# Circuit_schematic.net
KiCad netlist of a schematic drawn in EAGLE
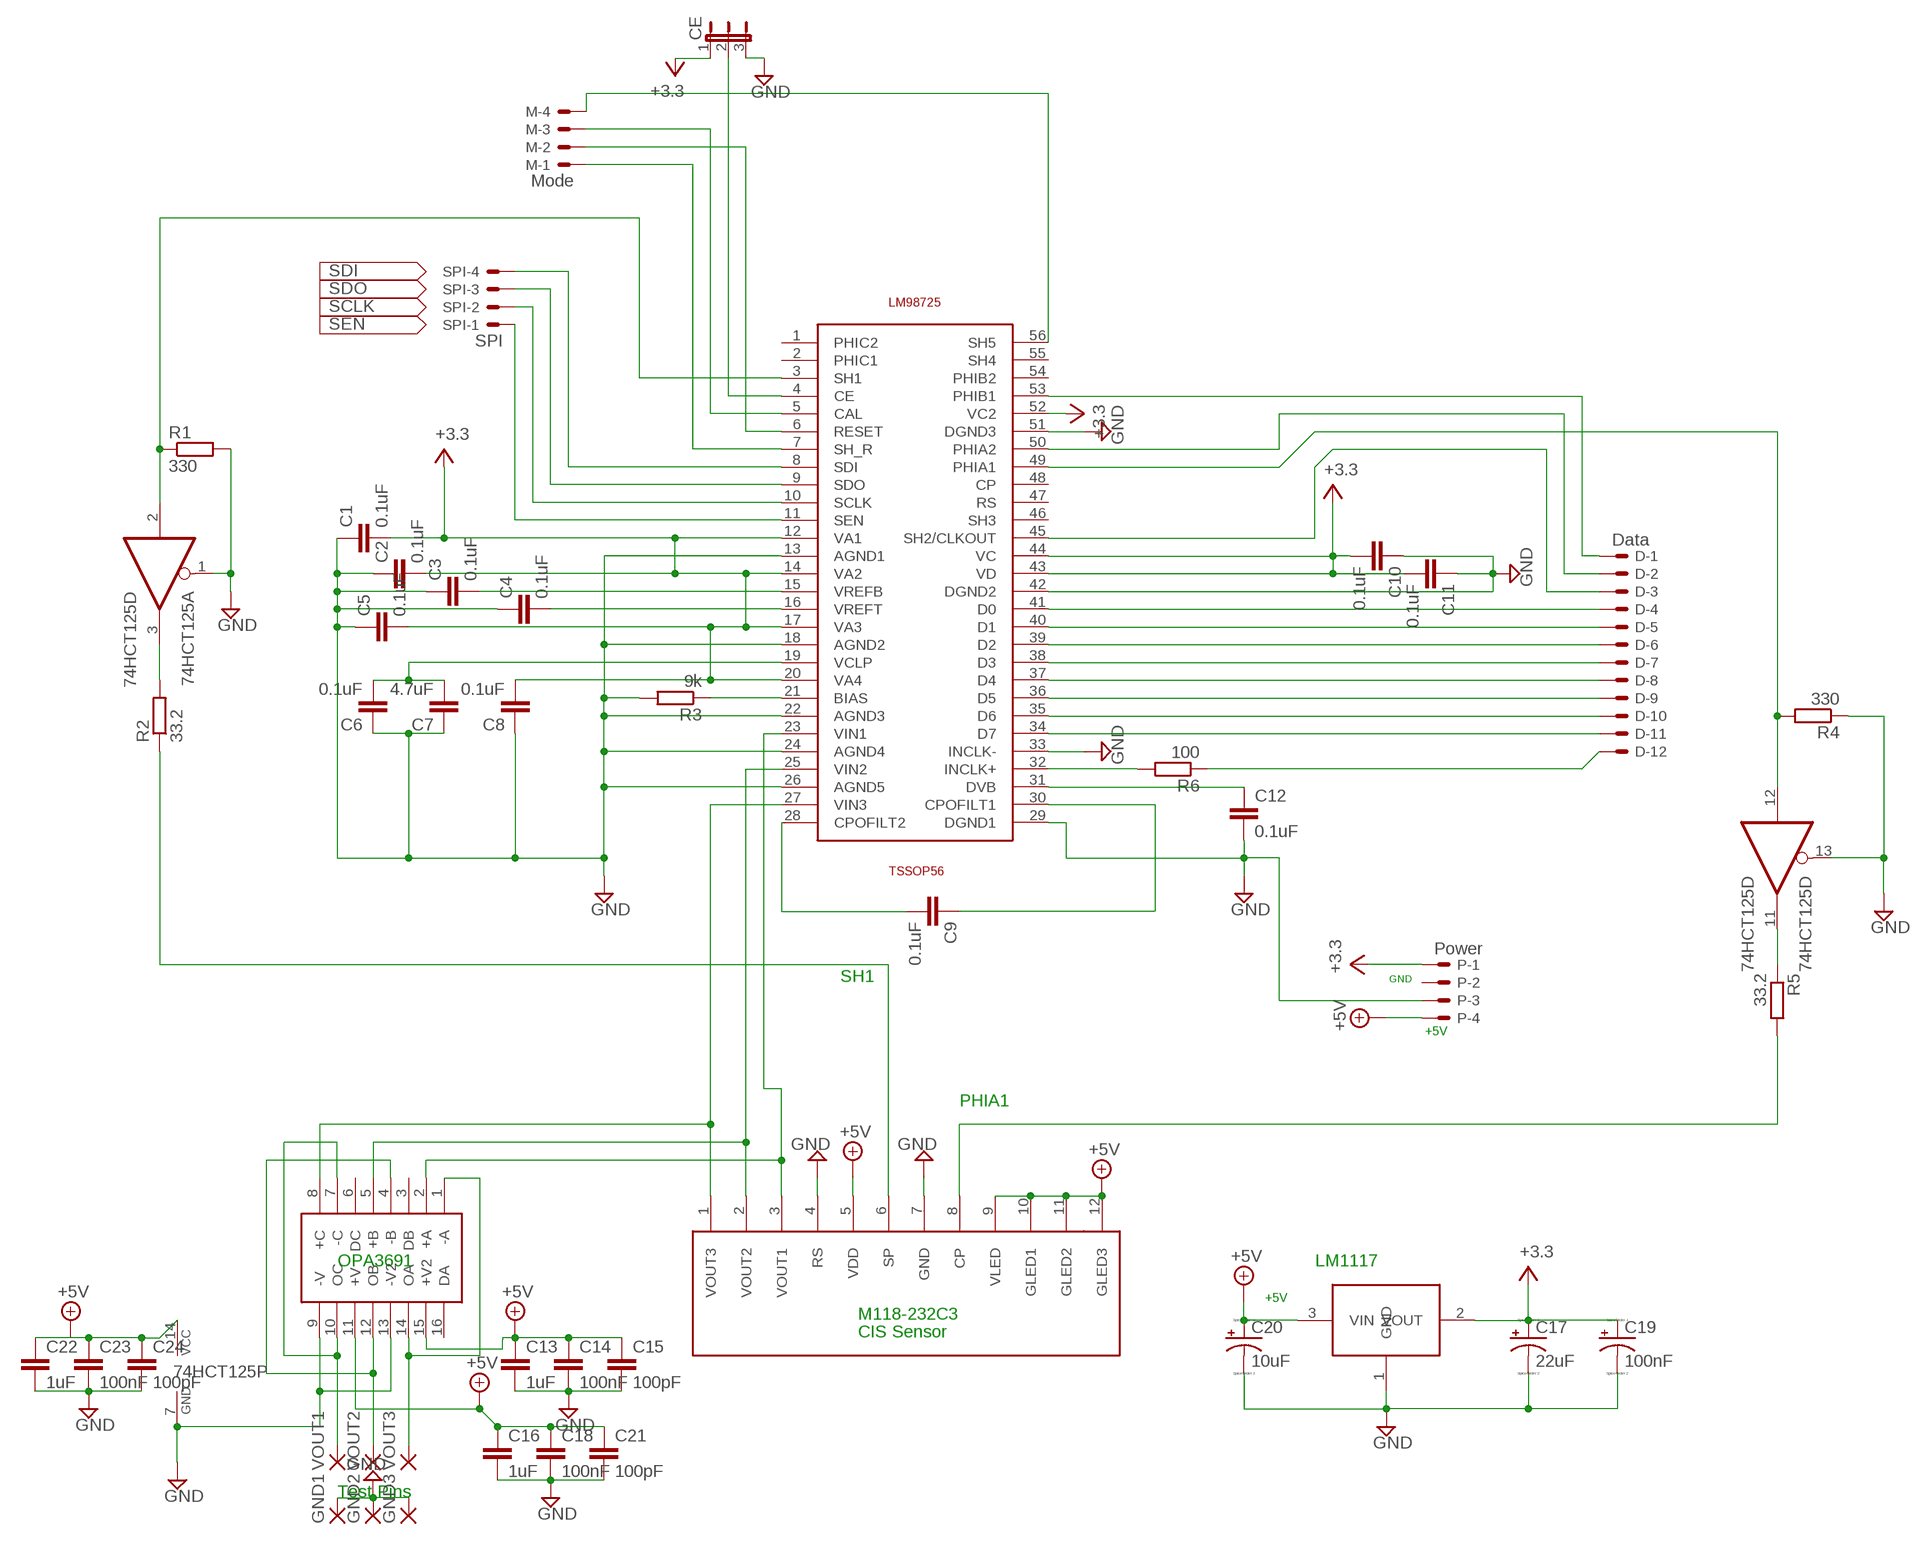
[diagram p0: schematic, sheet 1]

(export (version "E")
  (design (tool "Eeschema 10.0.6"))
  (components
    (comp (ref "74HCT125")
      (value "74HCT125D")
      (footprint "eagle-import:SO14")
      (libsource (lib "eagle-import") (part "74125DHCT"))
    )
    (comp (ref "C1")
      (value "0.1uF")
      (footprint "eagle-import:C0603")
      (libsource (lib "eagle-import") (part "C-EUC0603"))
    )
    (comp (ref "C2")
      (value "0.1uF")
      (footprint "eagle-import:C0603")
      (libsource (lib "eagle-import") (part "C-EUC0603"))
    )
    (comp (ref "C3")
      (value "0.1uF")
      (footprint "eagle-import:C0603")
      (libsource (lib "eagle-import") (part "C-EUC0603"))
    )
    (comp (ref "C4")
      (value "0.1uF")
      (footprint "eagle-import:C0603")
      (libsource (lib "eagle-import") (part "C-EUC0603"))
    )
    (comp (ref "C5")
      (value "0.1uF")
      (footprint "eagle-import:C0603")
      (libsource (lib "eagle-import") (part "C-EUC0603"))
    )
    (comp (ref "C6")
      (value "0.1uF")
      (footprint "eagle-import:C0603")
      (libsource (lib "eagle-import") (part "C-EUC0603"))
    )
    (comp (ref "C7")
      (value "4.7uF")
      (footprint "eagle-import:C0603")
      (libsource (lib "eagle-import") (part "C-EUC0603"))
    )
    (comp (ref "C8")
      (value "0.1uF")
      (footprint "eagle-import:C0603")
      (libsource (lib "eagle-import") (part "C-EUC0603"))
    )
    (comp (ref "C9")
      (value "0.1uF")
      (footprint "eagle-import:C0603")
      (libsource (lib "eagle-import") (part "C-EUC0603"))
    )
    (comp (ref "C10")
      (value "0.1uF")
      (footprint "eagle-import:C0603")
      (libsource (lib "eagle-import") (part "C-EUC0603"))
    )
    (comp (ref "C11")
      (value "0.1uF")
      (footprint "eagle-import:C0603")
      (libsource (lib "eagle-import") (part "C-EUC0603"))
    )
    (comp (ref "C12")
      (value "0.1uF")
      (footprint "eagle-import:C0603")
      (libsource (lib "eagle-import") (part "C-EUC0603"))
    )
    (comp (ref "C13")
      (value "1uF")
      (footprint "eagle-import:C0603")
      (libsource (lib "eagle-import") (part "C-EUC0603"))
    )
    (comp (ref "C14")
      (value "100nF")
      (footprint "eagle-import:C0603")
      (libsource (lib "eagle-import") (part "C-EUC0603"))
    )
    (comp (ref "C15")
      (value "100pF")
      (footprint "eagle-import:C0603")
      (libsource (lib "eagle-import") (part "C-EUC0603"))
    )
    (comp (ref "C16")
      (value "1uF")
      (footprint "eagle-import:C0603")
      (libsource (lib "eagle-import") (part "C-EUC0603"))
    )
    (comp (ref "C17")
      (value "22uF")
      (footprint "eagle-import:D_7343-31W")
      (libsource (lib "eagle-import") (part "CPOL-USD/7343-31W"))
    )
    (comp (ref "C18")
      (value "100nF")
      (footprint "eagle-import:C0603")
      (libsource (lib "eagle-import") (part "C-EUC0603"))
    )
    (comp (ref "C19")
      (value "100nF")
      (footprint "eagle-import:A_3216-18W")
      (libsource (lib "eagle-import") (part "CPOL-USA/3216-18W"))
    )
    (comp (ref "C20")
      (value "10uF")
      (footprint "eagle-import:C_6032-28R")
      (libsource (lib "eagle-import") (part "CPOL-USC/6032-28R"))
    )
    (comp (ref "C21")
      (value "100pF")
      (footprint "eagle-import:C0603")
      (libsource (lib "eagle-import") (part "C-EUC0603"))
    )
    (comp (ref "C22")
      (value "1uF")
      (footprint "eagle-import:C0603")
      (libsource (lib "eagle-import") (part "C-EUC0603"))
    )
    (comp (ref "C23")
      (value "100nF")
      (footprint "eagle-import:C0603")
      (libsource (lib "eagle-import") (part "C-EUC0603"))
    )
    (comp (ref "C24")
      (value "100pF")
      (footprint "eagle-import:C0603")
      (libsource (lib "eagle-import") (part "C-EUC0603"))
    )
    (comp (ref "CE")
      (value "JP2E")
      (footprint "eagle-import:JP2")
      (libsource (lib "eagle-import") (part "JP2E"))
    )
    (comp (ref "D")
      (value "Data")
      (footprint "eagle-import:53048-12")
      (fields (field (name "MF") "WALDOM/MOLEX") (field (name "MPN") "53048-1210"))
      (libsource (lib "eagle-import") (part "53?-12048"))
    )
    (comp (ref "GND1")
      (value "3,17/1,3")
      (footprint "eagle-import:3,17_1,3")
      (libsource (lib "eagle-import") (part "3,17/1,3"))
    )
    (comp (ref "GND2")
      (value "3,17/1,3")
      (footprint "eagle-import:3,17_1,3")
      (libsource (lib "eagle-import") (part "3,17/1,3"))
    )
    (comp (ref "GND3")
      (value "3,17/1,3")
      (footprint "eagle-import:3,17_1,3")
      (libsource (lib "eagle-import") (part "3,17/1,3"))
    )
    (comp (ref "LM98725")
      (value "LM98725")
      (footprint "eagle-import:TSSOP56")
      (libsource (lib "eagle-import") (part "LM98725"))
    )
    (comp (ref "M")
      (value "Mode")
      (footprint "eagle-import:53048-04")
      (fields (field (name "MF") "MOLEX") (field (name "MPN") "53048-0410"))
      (libsource (lib "eagle-import") (part "53?-04048"))
    )
    (comp (ref "OPA3691")
      (value "OPA3691")
      (footprint "eagle-import:SO16")
      (libsource (lib "eagle-import") (part "OPA3691"))
    )
    (comp (ref "P")
      (value "Power")
      (footprint "eagle-import:53048-04")
      (fields (field (name "MF") "MOLEX") (field (name "MPN") "53048-0410"))
      (libsource (lib "eagle-import") (part "53?-04048"))
    )
    (comp (ref "R1")
      (value "330")
      (footprint "eagle-import:R0603")
      (libsource (lib "eagle-import") (part "R-EU_R0603"))
    )
    (comp (ref "R2")
      (value "33.2")
      (footprint "eagle-import:R0603")
      (libsource (lib "eagle-import") (part "R-EU_R0603"))
    )
    (comp (ref "R3")
      (value "9k")
      (footprint "eagle-import:R0603")
      (libsource (lib "eagle-import") (part "R-EU_R0603"))
    )
    (comp (ref "R4")
      (value "330")
      (footprint "eagle-import:R0603")
      (libsource (lib "eagle-import") (part "R-EU_R0603"))
    )
    (comp (ref "R5")
      (value "33.2")
      (footprint "eagle-import:R0603")
      (libsource (lib "eagle-import") (part "R-EU_R0603"))
    )
    (comp (ref "R6")
      (value "100")
      (footprint "eagle-import:R0603")
      (libsource (lib "eagle-import") (part "R-EU_R0603"))
    )
    (comp (ref "SENSOR")
      (value "CIS-M118118")
      (footprint "eagle-import:12PINPAD")
      (libsource (lib "eagle-import") (part "CIS-M118118"))
    )
    (comp (ref "SPI")
      (value "SPI")
      (footprint "eagle-import:53048-04")
      (fields (field (name "MF") "MOLEX") (field (name "MPN") "53048-0410"))
      (libsource (lib "eagle-import") (part "53?-04048"))
    )
    (comp (ref "U$2")
      (value "LM117")
      (footprint "eagle-import:LM")
      (libsource (lib "eagle-import") (part "LM117"))
    )
    (comp (ref "VOUT1")
      (value "3,17/1,3")
      (footprint "eagle-import:3,17_1,3")
      (libsource (lib "eagle-import") (part "3,17/1,3"))
    )
    (comp (ref "VOUT2")
      (value "3,17/1,3")
      (footprint "eagle-import:3,17_1,3")
      (libsource (lib "eagle-import") (part "3,17/1,3"))
    )
    (comp (ref "VOUT3")
      (value "3,17/1,3")
      (footprint "eagle-import:3,17_1,3")
      (libsource (lib "eagle-import") (part "3,17/1,3"))
    )
  )
  (nets
    (net (code "1") (name "+3.3") (class "Default")
      (node (ref "C1") (pin "2") (pinfunction "2_2") (pintype "passive"))
      (node (ref "C10") (pin "2") (pinfunction "2_2") (pintype "passive"))
      (node (ref "C11") (pin "2") (pinfunction "2_2") (pintype "passive"))
      (node (ref "C17") (pin "+") (pinfunction "+_+") (pintype "passive"))
      (node (ref "C19") (pin "+") (pinfunction "+_+") (pintype "passive"))
      (node (ref "C2") (pin "2") (pinfunction "2_2") (pintype "passive"))
      (node (ref "C5") (pin "2") (pinfunction "2_2") (pintype "passive"))
      (node (ref "C8") (pin "2") (pinfunction "2_2") (pintype "passive"))
      (node (ref "CE") (pin "1") (pinfunction "1_1") (pintype "passive"))
      (node (ref "LM98725") (pin "12") (pinfunction "VA1_12") (pintype "bidirectional"))
      (node (ref "LM98725") (pin "14") (pinfunction "VA2_14") (pintype "bidirectional"))
      (node (ref "LM98725") (pin "17") (pinfunction "VA3_17") (pintype "bidirectional"))
      (node (ref "LM98725") (pin "20") (pinfunction "VA4_20") (pintype "bidirectional"))
      (node (ref "LM98725") (pin "43") (pinfunction "VD_43") (pintype "bidirectional"))
      (node (ref "LM98725") (pin "44") (pinfunction "VC_44") (pintype "bidirectional"))
      (node (ref "LM98725") (pin "52") (pinfunction "VC2_52") (pintype "bidirectional"))
      (node (ref "P") (pin "1") (pinfunction "S_1") (pintype "passive"))
      (node (ref "U$2") (pin "2") (pinfunction "VOUT_2") (pintype "bidirectional"))
    )
    (net (code "2") (name "+5V") (class "Default")
      (node (ref "74HCT125") (pin "14") (pinfunction "VCC_14") (pintype "power_in"))
      (node (ref "C13") (pin "1") (pinfunction "1_1") (pintype "passive"))
      (node (ref "C14") (pin "1") (pinfunction "1_1") (pintype "passive"))
      (node (ref "C15") (pin "1") (pinfunction "1_1") (pintype "passive"))
      (node (ref "C16") (pin "1") (pinfunction "1_1") (pintype "passive"))
      (node (ref "C18") (pin "1") (pinfunction "1_1") (pintype "passive"))
      (node (ref "C20") (pin "+") (pinfunction "+_+") (pintype "passive"))
      (node (ref "C21") (pin "1") (pinfunction "1_1") (pintype "passive"))
      (node (ref "C22") (pin "1") (pinfunction "1_1") (pintype "passive"))
      (node (ref "C23") (pin "1") (pinfunction "1_1") (pintype "passive"))
      (node (ref "C24") (pin "1") (pinfunction "1_1") (pintype "passive"))
      (node (ref "OPA3691") (pin "11") (pinfunction "+V_11") (pintype "bidirectional"))
      (node (ref "OPA3691") (pin "15") (pinfunction "+V2_15") (pintype "bidirectional"))
      (node (ref "P") (pin "4") (pinfunction "S_4") (pintype "passive"))
      (node (ref "SENSOR") (pin "10") (pinfunction "GLED1_10") (pintype "bidirectional"))
      (node (ref "SENSOR") (pin "11") (pinfunction "GLED2_11") (pintype "bidirectional"))
      (node (ref "SENSOR") (pin "12") (pinfunction "GLED3_12") (pintype "bidirectional"))
      (node (ref "SENSOR") (pin "5") (pinfunction "VDD_5") (pintype "bidirectional"))
      (node (ref "SENSOR") (pin "9") (pinfunction "VLED_9") (pintype "bidirectional"))
      (node (ref "U$2") (pin "3") (pinfunction "VIN_3") (pintype "bidirectional"))
    )
    (net (code "3") (name "GND") (class "Default")
      (node (ref "74HCT125") (pin "1") (pinfunction "OE_1") (pintype "input"))
      (node (ref "74HCT125") (pin "13") (pinfunction "OE_13") (pintype "input"))
      (node (ref "74HCT125") (pin "7") (pinfunction "GND_7") (pintype "power_in"))
      (node (ref "C1") (pin "1") (pinfunction "1_1") (pintype "passive"))
      (node (ref "C10") (pin "1") (pinfunction "1_1") (pintype "passive"))
      (node (ref "C11") (pin "1") (pinfunction "1_1") (pintype "passive"))
      (node (ref "C12") (pin "2") (pinfunction "2_2") (pintype "passive"))
      (node (ref "C13") (pin "2") (pinfunction "2_2") (pintype "passive"))
      (node (ref "C14") (pin "2") (pinfunction "2_2") (pintype "passive"))
      (node (ref "C15") (pin "2") (pinfunction "2_2") (pintype "passive"))
      (node (ref "C16") (pin "2") (pinfunction "2_2") (pintype "passive"))
      (node (ref "C17") (pin "-") (pinfunction "-_-") (pintype "passive"))
      (node (ref "C18") (pin "2") (pinfunction "2_2") (pintype "passive"))
      (node (ref "C19") (pin "-") (pinfunction "-_-") (pintype "passive"))
      (node (ref "C2") (pin "1") (pinfunction "1_1") (pintype "passive"))
      (node (ref "C20") (pin "-") (pinfunction "-_-") (pintype "passive"))
      (node (ref "C21") (pin "2") (pinfunction "2_2") (pintype "passive"))
      (node (ref "C22") (pin "2") (pinfunction "2_2") (pintype "passive"))
      (node (ref "C23") (pin "2") (pinfunction "2_2") (pintype "passive"))
      (node (ref "C24") (pin "2") (pinfunction "2_2") (pintype "passive"))
      (node (ref "C3") (pin "1") (pinfunction "1_1") (pintype "passive"))
      (node (ref "C4") (pin "1") (pinfunction "1_1") (pintype "passive"))
      (node (ref "C5") (pin "1") (pinfunction "1_1") (pintype "passive"))
      (node (ref "C6") (pin "1") (pinfunction "1_1") (pintype "passive"))
      (node (ref "C7") (pin "1") (pinfunction "1_1") (pintype "passive"))
      (node (ref "C8") (pin "1") (pinfunction "1_1") (pintype "passive"))
      (node (ref "CE") (pin "3") (pinfunction "3_3") (pintype "passive"))
      (node (ref "GND1") (pin "1") (pinfunction "P_1") (pintype "passive"))
      (node (ref "GND2") (pin "1") (pinfunction "P_1") (pintype "passive"))
      (node (ref "GND3") (pin "1") (pinfunction "P_1") (pintype "passive"))
      (node (ref "LM98725") (pin "13") (pinfunction "AGND1_13") (pintype "bidirectional"))
      (node (ref "LM98725") (pin "18") (pinfunction "AGND2_18") (pintype "bidirectional"))
      (node (ref "LM98725") (pin "22") (pinfunction "AGND3_22") (pintype "bidirectional"))
      (node (ref "LM98725") (pin "24") (pinfunction "AGND4_24") (pintype "bidirectional"))
      (node (ref "LM98725") (pin "26") (pinfunction "AGND5_26") (pintype "bidirectional"))
      (node (ref "LM98725") (pin "29") (pinfunction "DGND1_29") (pintype "bidirectional"))
      (node (ref "LM98725") (pin "33") (pinfunction "INCLK-_33") (pintype "bidirectional"))
      (node (ref "LM98725") (pin "42") (pinfunction "DGND2_42") (pintype "bidirectional"))
      (node (ref "LM98725") (pin "51") (pinfunction "DGND3_51") (pintype "bidirectional"))
      (node (ref "OPA3691") (pin "13") (pinfunction "-V2_13") (pintype "bidirectional"))
      (node (ref "OPA3691") (pin "9") (pinfunction "-V_9") (pintype "bidirectional"))
      (node (ref "P") (pin "3") (pinfunction "S_3") (pintype "passive"))
      (node (ref "R1") (pin "2") (pinfunction "2_2") (pintype "passive"))
      (node (ref "R3") (pin "2") (pinfunction "2_2") (pintype "passive"))
      (node (ref "R4") (pin "1") (pinfunction "1_1") (pintype "passive"))
      (node (ref "SENSOR") (pin "4") (pinfunction "RS_4") (pintype "bidirectional"))
      (node (ref "SENSOR") (pin "7") (pinfunction "GND_7") (pintype "bidirectional"))
      (node (ref "U$2") (pin "1") (pinfunction "GND_1") (pintype "bidirectional"))
    )
    (net (code "4") (name "Net-(74HCT125A-I)") (class "Default")
      (node (ref "74HCT125") (pin "2") (pinfunction "I_2") (pintype "input"))
      (node (ref "LM98725") (pin "3") (pinfunction "SH1_3") (pintype "bidirectional"))
      (node (ref "R1") (pin "1") (pinfunction "1_1") (pintype "passive"))
    )
    (net (code "5") (name "Net-(74HCT125A-O)") (class "Default")
      (node (ref "74HCT125") (pin "3") (pinfunction "O_3") (pintype "tri_state"))
      (node (ref "R2") (pin "2") (pinfunction "2_2") (pintype "passive"))
    )
    (net (code "6") (name "Net-(74HCT125D-I)") (class "Default")
      (node (ref "74HCT125") (pin "12") (pinfunction "I_12") (pintype "input"))
      (node (ref "LM98725") (pin "49") (pinfunction "PHIA1_49") (pintype "bidirectional"))
      (node (ref "R4") (pin "2") (pinfunction "2_2") (pintype "passive"))
    )
    (net (code "7") (name "Net-(74HCT125D-O)") (class "Default")
      (node (ref "74HCT125") (pin "11") (pinfunction "O_11") (pintype "tri_state"))
      (node (ref "R5") (pin "1") (pinfunction "1_1") (pintype "passive"))
    )
    (net (code "8") (name "Net-(DA-S)") (class "Default")
      (node (ref "D") (pin "1") (pinfunction "S_1") (pintype "passive"))
      (node (ref "LM98725") (pin "53") (pinfunction "PHIB1_53") (pintype "bidirectional"))
    )
    (net (code "9") (name "Net-(DB-S)") (class "Default")
      (node (ref "D") (pin "10") (pinfunction "S_10") (pintype "passive"))
      (node (ref "LM98725") (pin "35") (pinfunction "D6_35") (pintype "bidirectional"))
    )
    (net (code "10") (name "Net-(DC-S)") (class "Default")
      (node (ref "D") (pin "11") (pinfunction "S_11") (pintype "passive"))
      (node (ref "LM98725") (pin "34") (pinfunction "D7_34") (pintype "bidirectional"))
    )
    (net (code "11") (name "Net-(DD-S)") (class "Default")
      (node (ref "D") (pin "12") (pinfunction "S_12") (pintype "passive"))
      (node (ref "R6") (pin "1") (pinfunction "1_1") (pintype "passive"))
    )
    (net (code "12") (name "Net-(DE-S)") (class "Default")
      (node (ref "D") (pin "2") (pinfunction "S_2") (pintype "passive"))
      (node (ref "LM98725") (pin "50") (pinfunction "PHIA2_50") (pintype "bidirectional"))
    )
    (net (code "13") (name "Net-(DF-S)") (class "Default")
      (node (ref "D") (pin "3") (pinfunction "S_3") (pintype "passive"))
      (node (ref "LM98725") (pin "45") (pinfunction "SH2/CLKOUT_45") (pintype "bidirectional"))
    )
    (net (code "14") (name "Net-(DG-S)") (class "Default")
      (node (ref "D") (pin "4") (pinfunction "S_4") (pintype "passive"))
      (node (ref "LM98725") (pin "41") (pinfunction "D0_41") (pintype "bidirectional"))
    )
    (net (code "15") (name "Net-(DH-S)") (class "Default")
      (node (ref "D") (pin "5") (pinfunction "S_5") (pintype "passive"))
      (node (ref "LM98725") (pin "40") (pinfunction "D1_40") (pintype "bidirectional"))
    )
    (net (code "16") (name "Net-(DI-S)") (class "Default")
      (node (ref "D") (pin "6") (pinfunction "S_6") (pintype "passive"))
      (node (ref "LM98725") (pin "39") (pinfunction "D2_39") (pintype "bidirectional"))
    )
    (net (code "17") (name "Net-(DJ-S)") (class "Default")
      (node (ref "D") (pin "7") (pinfunction "S_7") (pintype "passive"))
      (node (ref "LM98725") (pin "38") (pinfunction "D3_38") (pintype "bidirectional"))
    )
    (net (code "18") (name "Net-(DK-S)") (class "Default")
      (node (ref "D") (pin "8") (pinfunction "S_8") (pintype "passive"))
      (node (ref "LM98725") (pin "37") (pinfunction "D4_37") (pintype "bidirectional"))
    )
    (net (code "19") (name "Net-(DL-S)") (class "Default")
      (node (ref "D") (pin "9") (pinfunction "S_9") (pintype "passive"))
      (node (ref "LM98725") (pin "36") (pinfunction "D5_36") (pintype "bidirectional"))
    )
    (net (code "20") (name "Net-(LM98725-BIAS)") (class "Default")
      (node (ref "LM98725") (pin "21") (pinfunction "BIAS_21") (pintype "bidirectional"))
      (node (ref "R3") (pin "1") (pinfunction "1_1") (pintype "passive"))
    )
    (net (code "21") (name "Net-(LM98725-CAL)") (class "Default")
      (node (ref "LM98725") (pin "5") (pinfunction "CAL_5") (pintype "bidirectional"))
      (node (ref "M") (pin "3") (pinfunction "S_3") (pintype "passive"))
    )
    (net (code "22") (name "Net-(LM98725-CE)") (class "Default")
      (node (ref "CE") (pin "2") (pinfunction "2_2") (pintype "passive"))
      (node (ref "LM98725") (pin "4") (pinfunction "CE_4") (pintype "bidirectional"))
    )
    (net (code "23") (name "Net-(LM98725-CPOFILT1)") (class "Default")
      (node (ref "C9") (pin "1") (pinfunction "1_1") (pintype "passive"))
      (node (ref "LM98725") (pin "30") (pinfunction "CPOFILT1_30") (pintype "bidirectional"))
    )
    (net (code "24") (name "Net-(LM98725-CPOFILT2)") (class "Default")
      (node (ref "C9") (pin "2") (pinfunction "2_2") (pintype "passive"))
      (node (ref "LM98725") (pin "28") (pinfunction "CPOFILT2_28") (pintype "bidirectional"))
    )
    (net (code "25") (name "Net-(LM98725-DVB)") (class "Default")
      (node (ref "C12") (pin "1") (pinfunction "1_1") (pintype "passive"))
      (node (ref "LM98725") (pin "31") (pinfunction "DVB_31") (pintype "bidirectional"))
    )
    (net (code "26") (name "Net-(LM98725-INCLK+)") (class "Default")
      (node (ref "LM98725") (pin "32") (pinfunction "INCLK+_32") (pintype "bidirectional"))
      (node (ref "R6") (pin "2") (pinfunction "2_2") (pintype "passive"))
    )
    (net (code "27") (name "Net-(LM98725-RESET)") (class "Default")
      (node (ref "LM98725") (pin "6") (pinfunction "RESET_6") (pintype "bidirectional"))
      (node (ref "M") (pin "2") (pinfunction "S_2") (pintype "passive"))
    )
    (net (code "28") (name "Net-(LM98725-SCLK)") (class "Default")
      (node (ref "LM98725") (pin "10") (pinfunction "SCLK_10") (pintype "bidirectional"))
      (node (ref "SPI") (pin "2") (pinfunction "S_2") (pintype "passive"))
    )
    (net (code "29") (name "Net-(LM98725-SDI)") (class "Default")
      (node (ref "LM98725") (pin "8") (pinfunction "SDI_8") (pintype "bidirectional"))
      (node (ref "SPI") (pin "4") (pinfunction "S_4") (pintype "passive"))
    )
    (net (code "30") (name "Net-(LM98725-SDO)") (class "Default")
      (node (ref "LM98725") (pin "9") (pinfunction "SDO_9") (pintype "bidirectional"))
      (node (ref "SPI") (pin "3") (pinfunction "S_3") (pintype "passive"))
    )
    (net (code "31") (name "Net-(LM98725-SEN)") (class "Default")
      (node (ref "LM98725") (pin "11") (pinfunction "SEN_11") (pintype "bidirectional"))
      (node (ref "SPI") (pin "1") (pinfunction "S_1") (pintype "passive"))
    )
    (net (code "32") (name "Net-(LM98725-SH5)") (class "Default")
      (node (ref "LM98725") (pin "56") (pinfunction "SH5_56") (pintype "bidirectional"))
      (node (ref "M") (pin "4") (pinfunction "S_4") (pintype "passive"))
    )
    (net (code "33") (name "Net-(LM98725-SH_R)") (class "Default")
      (node (ref "LM98725") (pin "7") (pinfunction "SH_R_7") (pintype "bidirectional"))
      (node (ref "M") (pin "1") (pinfunction "S_1") (pintype "passive"))
    )
    (net (code "34") (name "Net-(LM98725-VCLP)") (class "Default")
      (node (ref "C6") (pin "2") (pinfunction "2_2") (pintype "passive"))
      (node (ref "C7") (pin "2") (pinfunction "2_2") (pintype "passive"))
      (node (ref "LM98725") (pin "19") (pinfunction "VCLP_19") (pintype "bidirectional"))
    )
    (net (code "35") (name "Net-(LM98725-VIN1)") (class "Default")
      (node (ref "LM98725") (pin "23") (pinfunction "VIN1_23") (pintype "bidirectional"))
      (node (ref "OPA3691") (pin "2") (pinfunction "+A_2") (pintype "bidirectional"))
      (node (ref "SENSOR") (pin "3") (pinfunction "VOUT1_3") (pintype "bidirectional"))
    )
    (net (code "36") (name "Net-(LM98725-VIN2)") (class "Default")
      (node (ref "LM98725") (pin "25") (pinfunction "VIN2_25") (pintype "bidirectional"))
      (node (ref "OPA3691") (pin "5") (pinfunction "+B_5") (pintype "bidirectional"))
      (node (ref "SENSOR") (pin "2") (pinfunction "VOUT2_2") (pintype "bidirectional"))
    )
    (net (code "37") (name "Net-(LM98725-VIN3)") (class "Default")
      (node (ref "LM98725") (pin "27") (pinfunction "VIN3_27") (pintype "bidirectional"))
      (node (ref "OPA3691") (pin "8") (pinfunction "+C_8") (pintype "bidirectional"))
      (node (ref "SENSOR") (pin "1") (pinfunction "VOUT3_1") (pintype "bidirectional"))
    )
    (net (code "38") (name "Net-(LM98725-VREFB)") (class "Default")
      (node (ref "C3") (pin "2") (pinfunction "2_2") (pintype "passive"))
      (node (ref "LM98725") (pin "15") (pinfunction "VREFB_15") (pintype "bidirectional"))
    )
    (net (code "39") (name "Net-(LM98725-VREFT)") (class "Default")
      (node (ref "C4") (pin "2") (pinfunction "2_2") (pintype "passive"))
      (node (ref "LM98725") (pin "16") (pinfunction "VREFT_16") (pintype "bidirectional"))
    )
    (net (code "40") (name "Net-(OPA3691--A)") (class "Default")
      (node (ref "OPA3691") (pin "1") (pinfunction "-A_1") (pintype "bidirectional"))
      (node (ref "OPA3691") (pin "14") (pinfunction "OA_14") (pintype "bidirectional"))
      (node (ref "VOUT3") (pin "1") (pinfunction "P_1") (pintype "passive"))
    )
    (net (code "41") (name "Net-(OPA3691--B)") (class "Default")
      (node (ref "OPA3691") (pin "12") (pinfunction "OB_12") (pintype "bidirectional"))
      (node (ref "OPA3691") (pin "4") (pinfunction "-B_4") (pintype "bidirectional"))
      (node (ref "VOUT2") (pin "1") (pinfunction "P_1") (pintype "passive"))
    )
    (net (code "42") (name "Net-(OPA3691--C)") (class "Default")
      (node (ref "OPA3691") (pin "10") (pinfunction "OC_10") (pintype "bidirectional"))
      (node (ref "OPA3691") (pin "7") (pinfunction "-C_7") (pintype "bidirectional"))
      (node (ref "VOUT1") (pin "1") (pinfunction "P_1") (pintype "passive"))
    )
    (net (code "43") (name "Net-(SENSOR-CP)") (class "Default")
      (node (ref "R5") (pin "2") (pinfunction "2_2") (pintype "passive"))
      (node (ref "SENSOR") (pin "8") (pinfunction "CP_8") (pintype "bidirectional"))
    )
    (net (code "44") (name "Net-(SENSOR-SP)") (class "Default")
      (node (ref "R2") (pin "1") (pinfunction "1_1") (pintype "passive"))
      (node (ref "SENSOR") (pin "6") (pinfunction "SP_6") (pintype "bidirectional"))
    )
    (net (code "45") (name "unconnected-(LM98725-CP-Pad48)") (class "Default")
      (node (ref "LM98725") (pin "48") (pinfunction "CP_48") (pintype "bidirectional"))
    )
    (net (code "46") (name "unconnected-(LM98725-PHIB2-Pad54)") (class "Default")
      (node (ref "LM98725") (pin "54") (pinfunction "PHIB2_54") (pintype "bidirectional"))
    )
    (net (code "47") (name "unconnected-(LM98725-PHIC1-Pad2)") (class "Default")
      (node (ref "LM98725") (pin "2") (pinfunction "PHIC1_2") (pintype "bidirectional"))
    )
    (net (code "48") (name "unconnected-(LM98725-PHIC2-Pad1)") (class "Default")
      (node (ref "LM98725") (pin "1") (pinfunction "PHIC2_1") (pintype "bidirectional"))
    )
    (net (code "49") (name "unconnected-(LM98725-RS-Pad47)") (class "Default")
      (node (ref "LM98725") (pin "47") (pinfunction "RS_47") (pintype "bidirectional"))
    )
    (net (code "50") (name "unconnected-(LM98725-SH3-Pad46)") (class "Default")
      (node (ref "LM98725") (pin "46") (pinfunction "SH3_46") (pintype "bidirectional"))
    )
    (net (code "51") (name "unconnected-(LM98725-SH4-Pad55)") (class "Default")
      (node (ref "LM98725") (pin "55") (pinfunction "SH4_55") (pintype "bidirectional"))
    )
    (net (code "52") (name "unconnected-(OPA3691-DA-Pad16)") (class "Default")
      (node (ref "OPA3691") (pin "16") (pinfunction "DA_16") (pintype "bidirectional"))
    )
    (net (code "53") (name "unconnected-(OPA3691-DB-Pad3)") (class "Default")
      (node (ref "OPA3691") (pin "3") (pinfunction "DB_3") (pintype "bidirectional"))
    )
    (net (code "54") (name "unconnected-(OPA3691-DC-Pad6)") (class "Default")
      (node (ref "OPA3691") (pin "6") (pinfunction "DC_6") (pintype "bidirectional"))
    )
    (net (code "55") (name "unconnected-(PB-S-Pad2)") (class "Default")
      (node (ref "P") (pin "2") (pinfunction "S_2") (pintype "passive"))
    )
  )
)
